# RiseUpTop.net
KiCad netlist of a schematic drawn in EAGLE
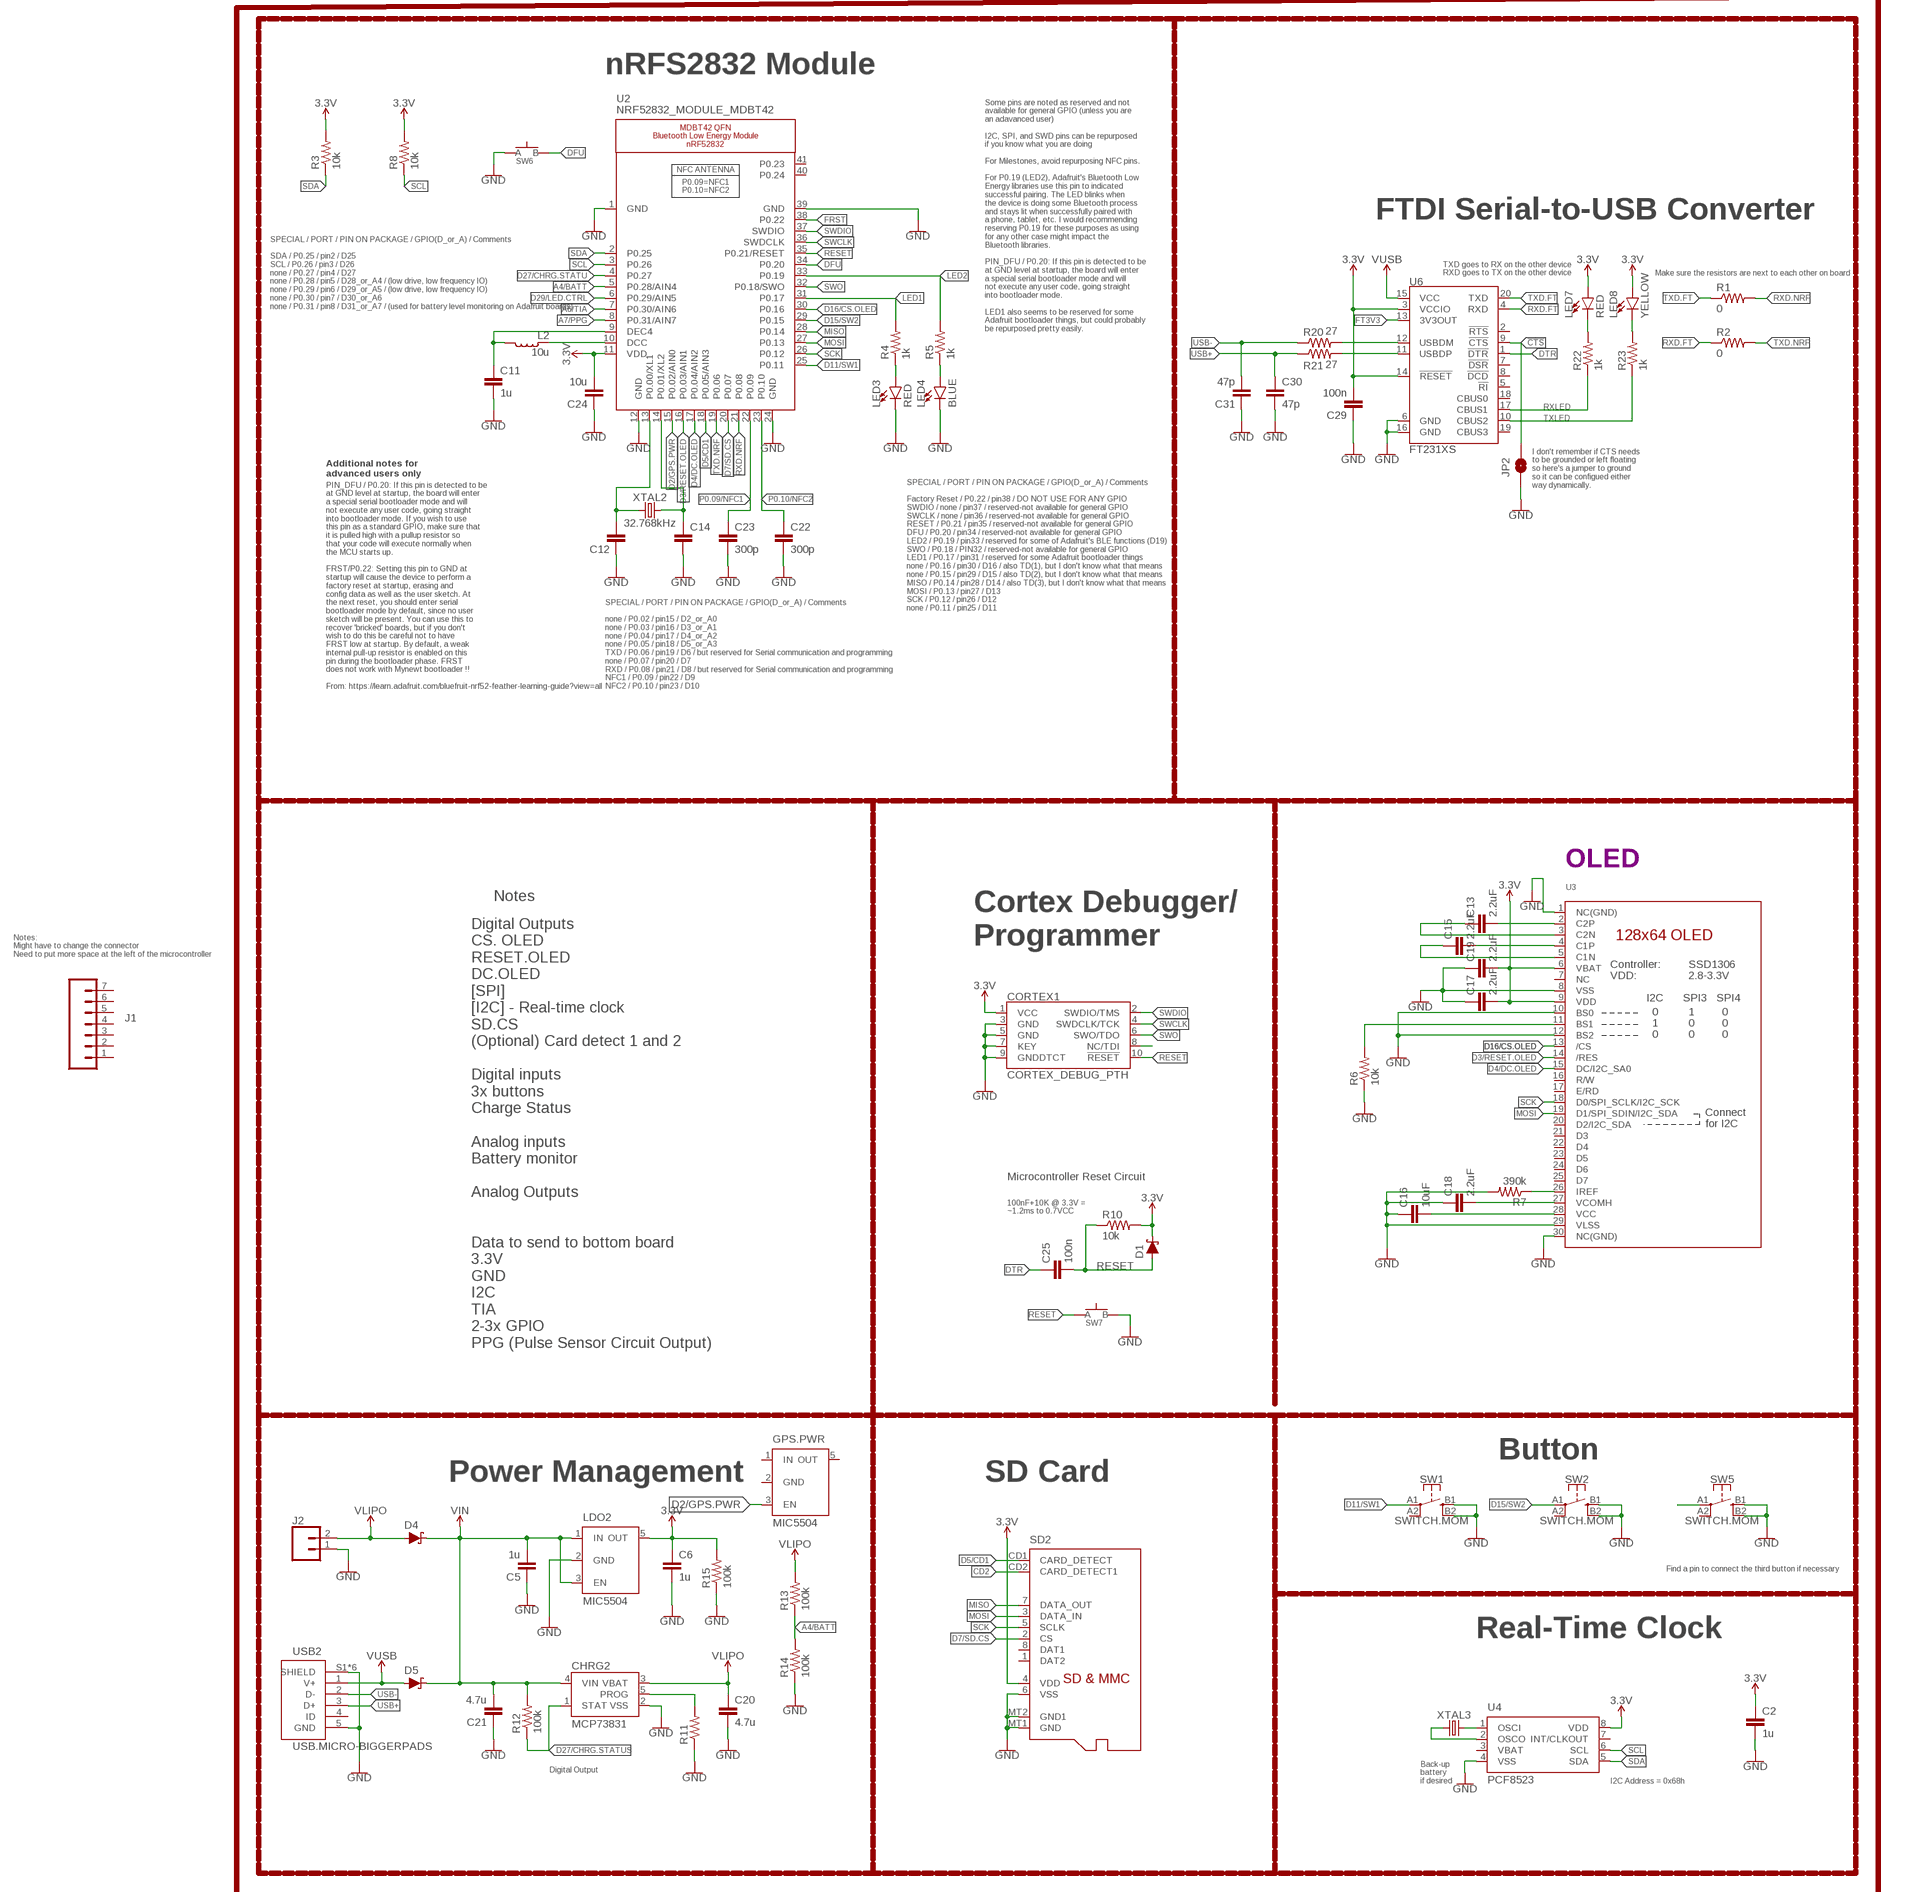
[diagram p0: schematic, sheet 1, part 1 of 2]
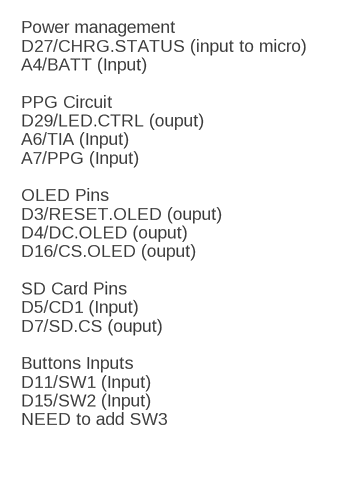
[diagram p1: schematic, sheet 1, part 2 of 2]

(export (version "E")
  (design (tool "Eeschema 10.0.6"))
  (components
    (comp (ref "C2")
      (value "1u")
      (footprint "eagle-import:C0603")
      (libsource (lib "eagle-import") (part "CAPACITOR0603"))
    )
    (comp (ref "C5")
      (value "1u")
      (footprint "eagle-import:C0603")
      (libsource (lib "eagle-import") (part "CAPACITOR0603"))
    )
    (comp (ref "C6")
      (value "1u")
      (footprint "eagle-import:C0603")
      (libsource (lib "eagle-import") (part "CAPACITOR0603"))
    )
    (comp (ref "C11")
      (value "1u")
      (footprint "eagle-import:C0603")
      (libsource (lib "eagle-import") (part "CAPACITOR0603"))
    )
    (comp (ref "C12")
      (value "CAPACITOR0603")
      (footprint "eagle-import:C0603")
      (libsource (lib "eagle-import") (part "CAPACITOR0603"))
    )
    (comp (ref "C13")
      (value "2.2uF")
      (footprint "eagle-import:C0402")
      (libsource (lib "eagle-import") (part "CAPACITOR0402"))
    )
    (comp (ref "C14")
      (value "CAPACITOR0603")
      (footprint "eagle-import:C0603")
      (libsource (lib "eagle-import") (part "CAPACITOR0603"))
    )
    (comp (ref "C15")
      (value "2.2uF")
      (footprint "eagle-import:C0402")
      (libsource (lib "eagle-import") (part "CAPACITOR0402"))
    )
    (comp (ref "C16")
      (value "10uF")
      (footprint "eagle-import:C0603")
      (libsource (lib "eagle-import") (part "CAPACITOR0603"))
    )
    (comp (ref "C17")
      (value "2.2uF")
      (footprint "eagle-import:C0402")
      (libsource (lib "eagle-import") (part "CAPACITOR0402"))
    )
    (comp (ref "C18")
      (value "2.2uF")
      (footprint "eagle-import:C0402")
      (libsource (lib "eagle-import") (part "CAPACITOR0402"))
    )
    (comp (ref "C19")
      (value "2.2uF")
      (footprint "eagle-import:C0402")
      (libsource (lib "eagle-import") (part "CAPACITOR0402"))
    )
    (comp (ref "C20")
      (value "4.7u")
      (footprint "eagle-import:C0603")
      (libsource (lib "eagle-import") (part "CAPACITOR0603"))
    )
    (comp (ref "C21")
      (value "4.7u")
      (footprint "eagle-import:C0603")
      (libsource (lib "eagle-import") (part "CAPACITOR0603"))
    )
    (comp (ref "C22")
      (value "300p")
      (footprint "eagle-import:C0603")
      (libsource (lib "eagle-import") (part "CAPACITOR0603"))
    )
    (comp (ref "C23")
      (value "300p")
      (footprint "eagle-import:C0603")
      (libsource (lib "eagle-import") (part "CAPACITOR0603"))
    )
    (comp (ref "C24")
      (value "10u")
      (footprint "eagle-import:C0805")
      (libsource (lib "eagle-import") (part "CAPACITOR0805"))
    )
    (comp (ref "C25")
      (value "100n")
      (footprint "eagle-import:C0603")
      (libsource (lib "eagle-import") (part "CAPACITOR0603"))
    )
    (comp (ref "C29")
      (value "100n")
      (footprint "eagle-import:C0603")
      (libsource (lib "eagle-import") (part "CAPACITOR0603"))
    )
    (comp (ref "C30")
      (value "47p")
      (footprint "eagle-import:C0603")
      (libsource (lib "eagle-import") (part "CAPACITOR0603"))
    )
    (comp (ref "C31")
      (value "47p")
      (footprint "eagle-import:C0603")
      (libsource (lib "eagle-import") (part "CAPACITOR0603"))
    )
    (comp (ref "CHRG2")
      (value "MCP73831")
      (footprint "eagle-import:SOT23-5")
      (libsource (lib "eagle-import") (part "MCP73831"))
    )
    (comp (ref "CORTEX1")
      (value "CORTEX_DEBUG_PTH")
      (footprint "eagle-import:2X5-PTH-1.27MM")
      (libsource (lib "eagle-import") (part "CORTEX_DEBUG_PTH"))
    )
    (comp (ref "D1")
      (value "SCHOTTKY-USC")
      (footprint "eagle-import:USC")
      (libsource (lib "eagle-import") (part "SCHOTTKY-USC"))
    )
    (comp (ref "D4")
      (value "SCHOTTKY-USC")
      (footprint "eagle-import:USC")
      (libsource (lib "eagle-import") (part "SCHOTTKY-USC"))
    )
    (comp (ref "D5")
      (value "SCHOTTKY-USC")
      (footprint "eagle-import:USC")
      (libsource (lib "eagle-import") (part "SCHOTTKY-USC"))
    )
    (comp (ref "GPS.PWR")
      (value "MIC5504")
      (footprint "eagle-import:SOT23-5")
      (libsource (lib "eagle-import") (part "MIC5504"))
    )
    (comp (ref "J1")
      (value "CONN_07")
      (footprint "eagle-import:1X07")
      (libsource (lib "eagle-import") (part "CONN_07"))
    )
    (comp (ref "J2")
      (value "CONN_02")
      (footprint "eagle-import:1X02")
      (libsource (lib "eagle-import") (part "CONN_02"))
    )
    (comp (ref "JP2")
      (value "JUMPER-SMT_2_NO_SILK")
      (footprint "eagle-import:SMT-JUMPER_2_NO_SILK")
      (libsource (lib "eagle-import") (part "JUMPER-SMT_2_NO_SILK"))
    )
    (comp (ref "L2")
      (value "10u")
      (footprint "eagle-import:L0603")
      (libsource (lib "eagle-import") (part "INDUCTOR0603"))
    )
    (comp (ref "LDO2")
      (value "MIC5504")
      (footprint "eagle-import:SOT23-5")
      (libsource (lib "eagle-import") (part "MIC5504"))
    )
    (comp (ref "LED3")
      (value "RED")
      (footprint "eagle-import:LED-0603")
      (libsource (lib "eagle-import") (part "LED0603"))
    )
    (comp (ref "LED4")
      (value "BLUE")
      (footprint "eagle-import:LED-0603")
      (libsource (lib "eagle-import") (part "LED0603"))
    )
    (comp (ref "LED7")
      (value "RED")
      (footprint "eagle-import:LED-0603")
      (libsource (lib "eagle-import") (part "LED0603"))
    )
    (comp (ref "LED8")
      (value "YELLOW")
      (footprint "eagle-import:LED-0603")
      (libsource (lib "eagle-import") (part "LED0603"))
    )
    (comp (ref "R1")
      (value "0")
      (footprint "eagle-import:R0603")
      (libsource (lib "eagle-import") (part "RESISTOR0603"))
    )
    (comp (ref "R2")
      (value "0")
      (footprint "eagle-import:R0603")
      (libsource (lib "eagle-import") (part "RESISTOR0603"))
    )
    (comp (ref "R3")
      (value "10k")
      (footprint "eagle-import:R0603")
      (libsource (lib "eagle-import") (part "RESISTOR0603"))
    )
    (comp (ref "R4")
      (value "1k")
      (footprint "eagle-import:R0603")
      (libsource (lib "eagle-import") (part "RESISTOR0603"))
    )
    (comp (ref "R5")
      (value "1k")
      (footprint "eagle-import:R0603")
      (libsource (lib "eagle-import") (part "RESISTOR0603"))
    )
    (comp (ref "R6")
      (value "10k")
      (footprint "eagle-import:R0603")
      (libsource (lib "eagle-import") (part "RESISTOR0603"))
    )
    (comp (ref "R7")
      (value "390k")
      (footprint "eagle-import:R0603")
      (libsource (lib "eagle-import") (part "RESISTOR0603"))
    )
    (comp (ref "R8")
      (value "10k")
      (footprint "eagle-import:R0603")
      (libsource (lib "eagle-import") (part "RESISTOR0603"))
    )
    (comp (ref "R10")
      (value "10k")
      (footprint "eagle-import:R0603")
      (libsource (lib "eagle-import") (part "RESISTOR0603"))
    )
    (comp (ref "R11")
      (value "RESISTOR0603")
      (footprint "eagle-import:R0603")
      (libsource (lib "eagle-import") (part "RESISTOR0603"))
    )
    (comp (ref "R12")
      (value "100k")
      (footprint "eagle-import:R0603")
      (libsource (lib "eagle-import") (part "RESISTOR0603"))
    )
    (comp (ref "R13")
      (value "100k")
      (footprint "eagle-import:R0603")
      (libsource (lib "eagle-import") (part "RESISTOR0603"))
    )
    (comp (ref "R14")
      (value "100k")
      (footprint "eagle-import:R0603")
      (libsource (lib "eagle-import") (part "RESISTOR0603"))
    )
    (comp (ref "R15")
      (value "100k")
      (footprint "eagle-import:R0603")
      (libsource (lib "eagle-import") (part "RESISTOR0603"))
    )
    (comp (ref "R20")
      (value "27")
      (footprint "eagle-import:R0603")
      (libsource (lib "eagle-import") (part "RESISTOR0603"))
    )
    (comp (ref "R21")
      (value "27")
      (footprint "eagle-import:R0603")
      (libsource (lib "eagle-import") (part "RESISTOR0603"))
    )
    (comp (ref "R22")
      (value "1k")
      (footprint "eagle-import:R0603")
      (libsource (lib "eagle-import") (part "RESISTOR0603"))
    )
    (comp (ref "R23")
      (value "1k")
      (footprint "eagle-import:R0603")
      (libsource (lib "eagle-import") (part "RESISTOR0603"))
    )
    (comp (ref "SD2")
      (value "MICROSD")
      (footprint "eagle-import:MICROSD")
      (libsource (lib "eagle-import") (part "MICROSD"))
    )
    (comp (ref "SW1")
      (value "SWITCH.MOM")
      (footprint "eagle-import:TACTILE_SWITCH_SMD_6.2MM_TALL")
      (libsource (lib "eagle-import") (part "SWITCH.MOM"))
    )
    (comp (ref "SW2")
      (value "SWITCH.MOM")
      (footprint "eagle-import:TACTILE_SWITCH_SMD_6.2MM_TALL")
      (libsource (lib "eagle-import") (part "SWITCH.MOM"))
    )
    (comp (ref "SW5")
      (value "SWITCH.MOM")
      (footprint "eagle-import:TACTILE_SWITCH_SMD_6.2MM_TALL")
      (libsource (lib "eagle-import") (part "SWITCH.MOM"))
    )
    (comp (ref "SW6")
      (value "SPST-PTS830GG140-COPY.1-3")
      (footprint "eagle-import:BUTTON-GULLWING")
      (libsource (lib "eagle-import") (part "SPST-PTS830GG140-COPY.1-3"))
    )
    (comp (ref "SW7")
      (value "SPST-PTS830GG140-COPY.1-3")
      (footprint "eagle-import:BUTTON-GULLWING")
      (libsource (lib "eagle-import") (part "SPST-PTS830GG140-COPY.1-3"))
    )
    (comp (ref "U2")
      (value "NRF52832_MODULE_MDBT42")
      (footprint "eagle-import:BLE_MODULE_RAYTAC_MDBT42")
      (libsource (lib "eagle-import") (part "NRF52832_MODULE_MDBT42"))
    )
    (comp (ref "U3")
      (value "DISP_OLED_UG-2864HSWEG01-NO-WRAPAROUND")
      (footprint "eagle-import:UG-2864HSWEG01_0.96IN_NO-WRAPAROUND")
      (libsource (lib "eagle-import") (part "DISP_OLED_UG-2864HSWEG01-NO-WRAPAROUND"))
    )
    (comp (ref "U4")
      (value "PCF8523")
      (footprint "eagle-import:SO8")
      (libsource (lib "eagle-import") (part "PCF8523"))
    )
    (comp (ref "U6")
      (value "FT231XS")
      (footprint "eagle-import:SSOP20_L")
      (libsource (lib "eagle-import") (part "FT231XS"))
    )
    (comp (ref "USB2")
      (value "USB.MICRO-BIGGERPADS")
      (footprint "eagle-import:USB-MICRO-01.BIGGERPADS")
      (libsource (lib "eagle-import") (part "USB.MICRO-BIGGERPADS"))
    )
    (comp (ref "XTAL2")
      (value "32.768kHz")
      (footprint "eagle-import:2-SMD.NOLEAD.2.0MMTO1.2MM")
      (libsource (lib "eagle-import") (part "CRYSTALECS-.327-12.5-12-C-TR"))
    )
    (comp (ref "XTAL3")
      (value "32.7680kHz")
      (footprint "eagle-import:2-SMD.NOLEAD.2.0MMTO1.2MM")
      (fields (field (name "FREQ") "32.7680KHZ"))
      (libsource (lib "eagle-import") (part "CRYSTALECS-.327-12.5-12-C-TR"))
    )
  )
  (nets
    (net (code "1") (name "/RXLED") (class "Default")
      (node (ref "R22") (pin "1") (pinfunction "1_1") (pintype "passive"))
      (node (ref "U6") (pin "17") (pinfunction "CBUS1_17") (pintype "bidirectional"))
    )
    (net (code "2") (name "/TXLED") (class "Default")
      (node (ref "R23") (pin "1") (pinfunction "1_1") (pintype "passive"))
      (node (ref "U6") (pin "10") (pinfunction "CBUS2_10") (pintype "bidirectional"))
    )
    (net (code "3") (name "/VBAT") (class "Default")
      (node (ref "U4") (pin "3") (pinfunction "VBAT_3") (pintype "power_in"))
    )
    (net (code "4") (name "/~{CTS}") (class "Default")
      (node (ref "JP2") (pin "2") (pinfunction "2_2") (pintype "passive"))
      (node (ref "U6") (pin "9") (pinfunction "~{CTS}_9") (pintype "bidirectional"))
    )
    (net (code "5") (name "3.3V") (class "Default")
      (node (ref "C17") (pin "2") (pinfunction "2_2") (pintype "passive"))
      (node (ref "C19") (pin "2") (pinfunction "2_2") (pintype "passive"))
      (node (ref "C2") (pin "1") (pinfunction "1_1") (pintype "passive"))
      (node (ref "C24") (pin "2") (pinfunction "2_2") (pintype "passive"))
      (node (ref "C29") (pin "2") (pinfunction "2_2") (pintype "passive"))
      (node (ref "C6") (pin "1") (pinfunction "1_1") (pintype "passive"))
      (node (ref "CORTEX1") (pin "1") (pinfunction "VCC_1") (pintype "bidirectional"))
      (node (ref "D1") (pin "-") (pinfunction "C_-") (pintype "passive"))
      (node (ref "LDO2") (pin "5") (pinfunction "OUT_5") (pintype "bidirectional"))
      (node (ref "LED7") (pin "A") (pinfunction "A_A") (pintype "passive"))
      (node (ref "LED8") (pin "A") (pinfunction "A_A") (pintype "passive"))
      (node (ref "R10") (pin "2") (pinfunction "2_2") (pintype "passive"))
      (node (ref "R15") (pin "2") (pinfunction "2_2") (pintype "passive"))
      (node (ref "R3") (pin "2") (pinfunction "2_2") (pintype "passive"))
      (node (ref "R8") (pin "2") (pinfunction "2_2") (pintype "passive"))
      (node (ref "SD2") (pin "4") (pinfunction "VDD_4") (pintype "power_in"))
      (node (ref "U2") (pin "11") (pinfunction "VDD_11") (pintype "bidirectional"))
      (node (ref "U3") (pin "6") (pinfunction "VBAT_6") (pintype "input"))
      (node (ref "U3") (pin "9") (pinfunction "VDD_9") (pintype "power_in"))
      (node (ref "U4") (pin "8") (pinfunction "VDD_8") (pintype "power_in"))
      (node (ref "U6") (pin "14") (pinfunction "~{RESET}_14") (pintype "bidirectional"))
      (node (ref "U6") (pin "3") (pinfunction "VCCIO_3") (pintype "bidirectional"))
    )
    (net (code "6") (name "A4{slash}BATT") (class "Default")
      (node (ref "R13") (pin "1") (pinfunction "1_1") (pintype "passive"))
      (node (ref "R14") (pin "2") (pinfunction "2_2") (pintype "passive"))
      (node (ref "U2") (pin "5") (pinfunction "P0.28/AIN4_5") (pintype "bidirectional"))
    )
    (net (code "7") (name "A6{slash}TIA") (class "Default")
      (node (ref "U2") (pin "7") (pinfunction "P0.30/AIN6_7") (pintype "bidirectional"))
    )
    (net (code "8") (name "A7{slash}PPG") (class "Default")
      (node (ref "U2") (pin "8") (pinfunction "P0.31/AIN7_8") (pintype "bidirectional"))
    )
    (net (code "9") (name "CD2") (class "Default")
      (node (ref "SD2") (pin "CD2") (pinfunction "CARD_DETECT1_CD2") (pintype "passive"))
    )
    (net (code "10") (name "D2{slash}GPS.PWR") (class "Default")
      (node (ref "GPS.PWR") (pin "3") (pinfunction "EN_3") (pintype "bidirectional"))
      (node (ref "U2") (pin "15") (pinfunction "P0.02/AIN0_15") (pintype "bidirectional"))
    )
    (net (code "11") (name "D3{slash}RESET.OLED") (class "Default")
      (node (ref "U2") (pin "16") (pinfunction "P0.03/AIN1_16") (pintype "bidirectional"))
      (node (ref "U3") (pin "14") (pinfunction "/RES_14") (pintype "input"))
    )
    (net (code "12") (name "D4{slash}DC.OLED") (class "Default")
      (node (ref "U2") (pin "17") (pinfunction "P0.04/AIN2_17") (pintype "bidirectional"))
      (node (ref "U3") (pin "15") (pinfunction "DC/I2C_SA0_15") (pintype "input"))
    )
    (net (code "13") (name "D5{slash}CD1") (class "Default")
      (node (ref "SD2") (pin "CD1") (pinfunction "CARD_DETECT_CD1") (pintype "passive"))
      (node (ref "U2") (pin "18") (pinfunction "P0.05/AIN3_18") (pintype "bidirectional"))
    )
    (net (code "14") (name "D7{slash}SD.CS") (class "Default")
      (node (ref "SD2") (pin "2") (pinfunction "CS_2") (pintype "input"))
      (node (ref "U2") (pin "20") (pinfunction "P0.07_20") (pintype "bidirectional"))
    )
    (net (code "15") (name "D11{slash}SW1") (class "Default")
      (node (ref "SW1") (pin "A1") (pinfunction "1_A1") (pintype "passive"))
      (node (ref "U2") (pin "25") (pinfunction "P0.11_25") (pintype "bidirectional"))
    )
    (net (code "16") (name "D15{slash}SW2") (class "Default")
      (node (ref "SW2") (pin "A1") (pinfunction "1_A1") (pintype "passive"))
      (node (ref "U2") (pin "29") (pinfunction "P0.15_29") (pintype "bidirectional"))
    )
    (net (code "17") (name "D16{slash}CS.OLED") (class "Default")
      (node (ref "U2") (pin "30") (pinfunction "P0.16_30") (pintype "bidirectional"))
      (node (ref "U3") (pin "13") (pinfunction "/CS_13") (pintype "input"))
    )
    (net (code "18") (name "D27{slash}CHRG.STATU") (class "Default")
      (node (ref "U2") (pin "4") (pinfunction "P0.27_4") (pintype "bidirectional"))
    )
    (net (code "19") (name "D27{slash}CHRG.STATUS") (class "Default")
      (node (ref "CHRG2") (pin "1") (pinfunction "STAT_1") (pintype "output"))
      (node (ref "R12") (pin "1") (pinfunction "1_1") (pintype "passive"))
    )
    (net (code "20") (name "D29{slash}LED.CTRL") (class "Default")
      (node (ref "U2") (pin "6") (pinfunction "P0.29/AIN5_6") (pintype "bidirectional"))
    )
    (net (code "21") (name "DFU") (class "Default")
      (node (ref "SW6") (pin "3") (pinfunction "B_3") (pintype "bidirectional"))
      (node (ref "U2") (pin "34") (pinfunction "P0.20_34") (pintype "bidirectional"))
    )
    (net (code "22") (name "DTR") (class "Default")
      (node (ref "C25") (pin "1") (pinfunction "1_1") (pintype "passive"))
      (node (ref "U6") (pin "1") (pinfunction "~{DTR}_1") (pintype "bidirectional"))
    )
    (net (code "23") (name "FRST") (class "Default")
      (node (ref "U2") (pin "38") (pinfunction "P0.22_38") (pintype "bidirectional"))
    )
    (net (code "24") (name "FT3V3") (class "Default")
      (node (ref "U6") (pin "13") (pinfunction "3V3OUT_13") (pintype "bidirectional"))
    )
    (net (code "25") (name "GND") (class "Default")
      (node (ref "C11") (pin "2") (pinfunction "2_2") (pintype "passive"))
      (node (ref "C12") (pin "1") (pinfunction "1_1") (pintype "passive"))
      (node (ref "C14") (pin "2") (pinfunction "2_2") (pintype "passive"))
      (node (ref "C16") (pin "1") (pinfunction "1_1") (pintype "passive"))
      (node (ref "C17") (pin "1") (pinfunction "1_1") (pintype "passive"))
      (node (ref "C18") (pin "1") (pinfunction "1_1") (pintype "passive"))
      (node (ref "C19") (pin "1") (pinfunction "1_1") (pintype "passive"))
      (node (ref "C2") (pin "2") (pinfunction "2_2") (pintype "passive"))
      (node (ref "C20") (pin "2") (pinfunction "2_2") (pintype "passive"))
      (node (ref "C21") (pin "1") (pinfunction "1_1") (pintype "passive"))
      (node (ref "C22") (pin "2") (pinfunction "2_2") (pintype "passive"))
      (node (ref "C23") (pin "2") (pinfunction "2_2") (pintype "passive"))
      (node (ref "C24") (pin "1") (pinfunction "1_1") (pintype "passive"))
      (node (ref "C29") (pin "1") (pinfunction "1_1") (pintype "passive"))
      (node (ref "C30") (pin "2") (pinfunction "2_2") (pintype "passive"))
      (node (ref "C31") (pin "1") (pinfunction "1_1") (pintype "passive"))
      (node (ref "C5") (pin "1") (pinfunction "1_1") (pintype "passive"))
      (node (ref "C6") (pin "2") (pinfunction "2_2") (pintype "passive"))
      (node (ref "CHRG2") (pin "2") (pinfunction "VSS_2") (pintype "power_in"))
      (node (ref "CORTEX1") (pin "3") (pinfunction "GND_3") (pintype "bidirectional"))
      (node (ref "CORTEX1") (pin "5") (pinfunction "GND_5") (pintype "bidirectional"))
      (node (ref "CORTEX1") (pin "7") (pinfunction "KEY_7") (pintype "bidirectional"))
      (node (ref "CORTEX1") (pin "9") (pinfunction "GNDDTCT_9") (pintype "bidirectional"))
      (node (ref "J2") (pin "1") (pinfunction "1_1") (pintype "passive"))
      (node (ref "JP2") (pin "1") (pinfunction "1_1") (pintype "passive"))
      (node (ref "LDO2") (pin "2") (pinfunction "GND_2") (pintype "bidirectional"))
      (node (ref "LED3") (pin "C") (pinfunction "C_C") (pintype "passive"))
      (node (ref "LED4") (pin "C") (pinfunction "C_C") (pintype "passive"))
      (node (ref "R11") (pin "1") (pinfunction "1_1") (pintype "passive"))
      (node (ref "R14") (pin "1") (pinfunction "1_1") (pintype "passive"))
      (node (ref "R15") (pin "1") (pinfunction "1_1") (pintype "passive"))
      (node (ref "R6") (pin "1") (pinfunction "1_1") (pintype "passive"))
      (node (ref "R7") (pin "2") (pinfunction "2_2") (pintype "passive"))
      (node (ref "SD2") (pin "6") (pinfunction "VSS_6") (pintype "power_in"))
      (node (ref "SD2") (pin "MT1") (pinfunction "GND_MT1") (pintype "power_in"))
      (node (ref "SD2") (pin "MT2") (pinfunction "GND1_MT2") (pintype "power_in"))
      (node (ref "SW1") (pin "B1") (pinfunction "3_B1") (pintype "passive"))
      (node (ref "SW1") (pin "B2") (pinfunction "4_B2") (pintype "passive"))
      (node (ref "SW2") (pin "B1") (pinfunction "3_B1") (pintype "passive"))
      (node (ref "SW2") (pin "B2") (pinfunction "4_B2") (pintype "passive"))
      (node (ref "SW5") (pin "B1") (pinfunction "3_B1") (pintype "passive"))
      (node (ref "SW5") (pin "B2") (pinfunction "4_B2") (pintype "passive"))
      (node (ref "SW6") (pin "1") (pinfunction "A_1") (pintype "bidirectional"))
      (node (ref "SW7") (pin "3") (pinfunction "B_3") (pintype "bidirectional"))
      (node (ref "U2") (pin "1") (pinfunction "GND_1") (pintype "bidirectional"))
      (node (ref "U2") (pin "12") (pinfunction "GND_12") (pintype "bidirectional"))
      (node (ref "U2") (pin "24") (pinfunction "GND_24") (pintype "bidirectional"))
      (node (ref "U2") (pin "39") (pinfunction "GND_39") (pintype "bidirectional"))
      (node (ref "U3") (pin "1") (pinfunction "NC(GND)_1") (pintype "input"))
      (node (ref "U3") (pin "10") (pinfunction "BS0_10") (pintype "input"))
      (node (ref "U3") (pin "12") (pinfunction "BS2_12") (pintype "input"))
      (node (ref "U3") (pin "29") (pinfunction "VLSS_29") (pintype "power_in"))
      (node (ref "U3") (pin "30") (pinfunction "NC(GND)_30") (pintype "input"))
      (node (ref "U3") (pin "8") (pinfunction "VSS_8") (pintype "power_in"))
      (node (ref "U4") (pin "4") (pinfunction "VSS_4") (pintype "power_in"))
      (node (ref "U6") (pin "16") (pinfunction "GND_16") (pintype "bidirectional"))
      (node (ref "U6") (pin "6") (pinfunction "GND_6") (pintype "bidirectional"))
      (node (ref "USB2") (pin "5") (pinfunction "GND_5") (pintype "bidirectional"))
      (node (ref "USB2") (pin "S1") (pinfunction "SHIELD_S1") (pintype "bidirectional"))
      (node (ref "USB2") (pin "S2") (pinfunction "SHIELD_S2") (pintype "bidirectional"))
      (node (ref "USB2") (pin "S3") (pinfunction "SHIELD_S3") (pintype "bidirectional"))
      (node (ref "USB2") (pin "S4") (pinfunction "SHIELD_S4") (pintype "bidirectional"))
      (node (ref "USB2") (pin "S5") (pinfunction "SHIELD_S5") (pintype "bidirectional"))
      (node (ref "USB2") (pin "S6") (pinfunction "SHIELD_S6") (pintype "bidirectional"))
    )
    (net (code "26") (name "LED1") (class "Default")
      (node (ref "R4") (pin "2") (pinfunction "2_2") (pintype "passive"))
      (node (ref "U2") (pin "31") (pinfunction "P0.17_31") (pintype "bidirectional"))
    )
    (net (code "27") (name "LED2") (class "Default")
      (node (ref "R5") (pin "2") (pinfunction "2_2") (pintype "passive"))
      (node (ref "U2") (pin "33") (pinfunction "P0.19_33") (pintype "bidirectional"))
    )
    (net (code "28") (name "MISO") (class "Default")
      (node (ref "SD2") (pin "7") (pinfunction "DATA_OUT_7") (pintype "output"))
      (node (ref "U2") (pin "28") (pinfunction "P0.14_28") (pintype "bidirectional"))
    )
    (net (code "29") (name "MOSI") (class "Default")
      (node (ref "SD2") (pin "3") (pinfunction "DATA_IN_3") (pintype "input"))
      (node (ref "U2") (pin "27") (pinfunction "P0.13_27") (pintype "bidirectional"))
      (node (ref "U3") (pin "19") (pinfunction "D1/SPI_SDIN/I2C_SDA_19") (pintype "bidirectional"))
    )
    (net (code "30") (name "Net-(CHRG2-PROG)") (class "Default")
      (node (ref "CHRG2") (pin "5") (pinfunction "PROG_5") (pintype "input"))
      (node (ref "R11") (pin "2") (pinfunction "2_2") (pintype "passive"))
    )
    (net (code "31") (name "Net-(LED3-PadA)") (class "Default")
      (node (ref "LED3") (pin "A") (pinfunction "A_A") (pintype "passive"))
      (node (ref "R4") (pin "1") (pinfunction "1_1") (pintype "passive"))
    )
    (net (code "32") (name "Net-(LED4-PadA)") (class "Default")
      (node (ref "LED4") (pin "A") (pinfunction "A_A") (pintype "passive"))
      (node (ref "R5") (pin "1") (pinfunction "1_1") (pintype "passive"))
    )
    (net (code "33") (name "Net-(LED7-PadC)") (class "Default")
      (node (ref "LED7") (pin "C") (pinfunction "C_C") (pintype "passive"))
      (node (ref "R22") (pin "2") (pinfunction "2_2") (pintype "passive"))
    )
    (net (code "34") (name "Net-(LED8-PadC)") (class "Default")
      (node (ref "LED8") (pin "C") (pinfunction "C_C") (pintype "passive"))
      (node (ref "R23") (pin "2") (pinfunction "2_2") (pintype "passive"))
    )
    (net (code "35") (name "Net-(U2-DCC)") (class "Default")
      (node (ref "L2") (pin "1") (pinfunction "1_1") (pintype "passive"))
      (node (ref "U2") (pin "10") (pinfunction "DCC_10") (pintype "bidirectional"))
    )
    (net (code "36") (name "Net-(U2-DEC4)") (class "Default")
      (node (ref "C11") (pin "1") (pinfunction "1_1") (pintype "passive"))
      (node (ref "L2") (pin "2") (pinfunction "2_2") (pintype "passive"))
      (node (ref "U2") (pin "9") (pinfunction "DEC4_9") (pintype "bidirectional"))
    )
    (net (code "37") (name "Net-(U2-P0.00{slash}XL1)") (class "Default")
      (node (ref "C12") (pin "2") (pinfunction "2_2") (pintype "passive"))
      (node (ref "U2") (pin "13") (pinfunction "P0.00/XL1_13") (pintype "bidirectional"))
      (node (ref "XTAL2") (pin "P$1") (pinfunction "1_P$1") (pintype "passive"))
    )
    (net (code "38") (name "Net-(U2-P0.01{slash}XL2)") (class "Default")
      (node (ref "C14") (pin "1") (pinfunction "1_1") (pintype "passive"))
      (node (ref "U2") (pin "14") (pinfunction "P0.01/XL2_14") (pintype "bidirectional"))
      (node (ref "XTAL2") (pin "P$2") (pinfunction "2_P$2") (pintype "passive"))
    )
    (net (code "39") (name "Net-(U3-BS1)") (class "Default")
      (node (ref "R6") (pin "2") (pinfunction "2_2") (pintype "passive"))
      (node (ref "U3") (pin "11") (pinfunction "BS1_11") (pintype "input"))
    )
    (net (code "40") (name "Net-(U3-C1N)") (class "Default")
      (node (ref "C15") (pin "1") (pinfunction "1_1") (pintype "passive"))
      (node (ref "U3") (pin "5") (pinfunction "C1N_5") (pintype "input"))
    )
    (net (code "41") (name "Net-(U3-C1P)") (class "Default")
      (node (ref "C15") (pin "2") (pinfunction "2_2") (pintype "passive"))
      (node (ref "U3") (pin "4") (pinfunction "C1P_4") (pintype "input"))
    )
    (net (code "42") (name "Net-(U3-C2N)") (class "Default")
      (node (ref "C13") (pin "1") (pinfunction "1_1") (pintype "passive"))
      (node (ref "U3") (pin "3") (pinfunction "C2N_3") (pintype "input"))
    )
    (net (code "43") (name "Net-(U3-C2P)") (class "Default")
      (node (ref "C13") (pin "2") (pinfunction "2_2") (pintype "passive"))
      (node (ref "U3") (pin "2") (pinfunction "C2P_2") (pintype "input"))
    )
    (net (code "44") (name "Net-(U3-IREF)") (class "Default")
      (node (ref "R7") (pin "1") (pinfunction "1_1") (pintype "passive"))
      (node (ref "U3") (pin "26") (pinfunction "IREF_26") (pintype "input"))
    )
    (net (code "45") (name "Net-(U3-VCC)") (class "Default")
      (node (ref "C16") (pin "2") (pinfunction "2_2") (pintype "passive"))
      (node (ref "U3") (pin "28") (pinfunction "VCC_28") (pintype "power_in"))
    )
    (net (code "46") (name "Net-(U3-VCOMH)") (class "Default")
      (node (ref "C18") (pin "2") (pinfunction "2_2") (pintype "passive"))
      (node (ref "U3") (pin "27") (pinfunction "VCOMH_27") (pintype "output"))
    )
    (net (code "47") (name "Net-(U4-OSCI)") (class "Default")
      (node (ref "U4") (pin "1") (pinfunction "OSCI_1") (pintype "bidirectional"))
      (node (ref "XTAL3") (pin "P$2") (pinfunction "2_P$2") (pintype "passive"))
    )
    (net (code "48") (name "Net-(U4-OSCO)") (class "Default")
      (node (ref "U4") (pin "2") (pinfunction "OSCO_2") (pintype "bidirectional"))
      (node (ref "XTAL3") (pin "P$1") (pinfunction "1_P$1") (pintype "passive"))
    )
    (net (code "49") (name "Net-(U6-USBDM)") (class "Default")
      (node (ref "R20") (pin "2") (pinfunction "2_2") (pintype "passive"))
      (node (ref "U6") (pin "12") (pinfunction "USBDM_12") (pintype "bidirectional"))
    )
    (net (code "50") (name "Net-(U6-USBDP)") (class "Default")
      (node (ref "R21") (pin "2") (pinfunction "2_2") (pintype "passive"))
      (node (ref "U6") (pin "11") (pinfunction "USBDP_11") (pintype "bidirectional"))
    )
    (net (code "51") (name "P0.09{slash}NFC1") (class "Default")
      (node (ref "C23") (pin "1") (pinfunction "1_1") (pintype "passive"))
      (node (ref "U2") (pin "22") (pinfunction "P0.09_22") (pintype "bidirectional"))
    )
    (net (code "52") (name "P0.10{slash}NFC2") (class "Default")
      (node (ref "C22") (pin "1") (pinfunction "1_1") (pintype "passive"))
      (node (ref "U2") (pin "23") (pinfunction "P0.10_23") (pintype "bidirectional"))
    )
    (net (code "53") (name "RESET") (class "Default")
      (node (ref "C25") (pin "2") (pinfunction "2_2") (pintype "passive"))
      (node (ref "CORTEX1") (pin "10") (pinfunction "~{RESET}_10") (pintype "bidirectional"))
      (node (ref "D1") (pin "+") (pinfunction "A_+") (pintype "passive"))
      (node (ref "R10") (pin "1") (pinfunction "1_1") (pintype "passive"))
      (node (ref "SW7") (pin "1") (pinfunction "A_1") (pintype "bidirectional"))
      (node (ref "U2") (pin "35") (pinfunction "P0.21/RESET_35") (pintype "bidirectional"))
    )
    (net (code "54") (name "RXD.FT") (class "Default")
      (node (ref "R2") (pin "1") (pinfunction "1_1") (pintype "passive"))
      (node (ref "U6") (pin "4") (pinfunction "RXD_4") (pintype "bidirectional"))
    )
    (net (code "55") (name "RXD.NRF") (class "Default")
      (node (ref "R1") (pin "2") (pinfunction "2_2") (pintype "passive"))
      (node (ref "U2") (pin "21") (pinfunction "P0.08_21") (pintype "bidirectional"))
    )
    (net (code "56") (name "SCK") (class "Default")
      (node (ref "SD2") (pin "5") (pinfunction "SCLK_5") (pintype "input"))
      (node (ref "U2") (pin "26") (pinfunction "P0.12_26") (pintype "bidirectional"))
      (node (ref "U3") (pin "18") (pinfunction "D0/SPI_SCLK/I2C_SCK_18") (pintype "bidirectional"))
    )
    (net (code "57") (name "SCL") (class "Default")
      (node (ref "R8") (pin "1") (pinfunction "1_1") (pintype "passive"))
      (node (ref "U2") (pin "3") (pinfunction "P0.26_3") (pintype "bidirectional"))
      (node (ref "U4") (pin "6") (pinfunction "SCL_6") (pintype "bidirectional"))
    )
    (net (code "58") (name "SDA") (class "Default")
      (node (ref "R3") (pin "1") (pinfunction "1_1") (pintype "passive"))
      (node (ref "U2") (pin "2") (pinfunction "P0.25_2") (pintype "bidirectional"))
      (node (ref "U4") (pin "5") (pinfunction "SDA_5") (pintype "bidirectional"))
    )
    (net (code "59") (name "SWCLK") (class "Default")
      (node (ref "CORTEX1") (pin "4") (pinfunction "SWDCLK/TCK_4") (pintype "bidirectional"))
      (node (ref "U2") (pin "36") (pinfunction "SWDCLK_36") (pintype "bidirectional"))
    )
    (net (code "60") (name "SWDIO") (class "Default")
      (node (ref "CORTEX1") (pin "2") (pinfunction "SWDIO/TMS_2") (pintype "bidirectional"))
      (node (ref "U2") (pin "37") (pinfunction "SWDIO_37") (pintype "bidirectional"))
    )
    (net (code "61") (name "SWO") (class "Default")
      (node (ref "CORTEX1") (pin "6") (pinfunction "SWO/TDO_6") (pintype "bidirectional"))
      (node (ref "U2") (pin "32") (pinfunction "P0.18/SWO_32") (pintype "bidirectional"))
    )
    (net (code "62") (name "TXD.FT") (class "Default")
      (node (ref "R1") (pin "1") (pinfunction "1_1") (pintype "passive"))
      (node (ref "U6") (pin "20") (pinfunction "TXD_20") (pintype "bidirectional"))
    )
    (net (code "63") (name "TXD.NRF") (class "Default")
      (node (ref "R2") (pin "2") (pinfunction "2_2") (pintype "passive"))
      (node (ref "U2") (pin "19") (pinfunction "P0.06_19") (pintype "bidirectional"))
    )
    (net (code "64") (name "USB+") (class "Default")
      (node (ref "C30") (pin "1") (pinfunction "1_1") (pintype "passive"))
      (node (ref "R21") (pin "1") (pinfunction "1_1") (pintype "passive"))
      (node (ref "USB2") (pin "3") (pinfunction "D+_3") (pintype "bidirectional"))
    )
    (net (code "65") (name "USB-") (class "Default")
      (node (ref "C31") (pin "2") (pinfunction "2_2") (pintype "passive"))
      (node (ref "R20") (pin "1") (pinfunction "1_1") (pintype "passive"))
      (node (ref "USB2") (pin "2") (pinfunction "D-_2") (pintype "bidirectional"))
    )
    (net (code "66") (name "VIN") (class "Default")
      (node (ref "C21") (pin "2") (pinfunction "2_2") (pintype "passive"))
      (node (ref "C5") (pin "2") (pinfunction "2_2") (pintype "passive"))
      (node (ref "CHRG2") (pin "4") (pinfunction "VIN_4") (pintype "power_in"))
      (node (ref "D4") (pin "-") (pinfunction "C_-") (pintype "passive"))
      (node (ref "D5") (pin "-") (pinfunction "C_-") (pintype "passive"))
      (node (ref "LDO2") (pin "1") (pinfunction "IN_1") (pintype "bidirectional"))
      (node (ref "LDO2") (pin "3") (pinfunction "EN_3") (pintype "bidirectional"))
      (node (ref "R12") (pin "2") (pinfunction "2_2") (pintype "passive"))
    )
    (net (code "67") (name "VLIPO") (class "Default")
      (node (ref "C20") (pin "1") (pinfunction "1_1") (pintype "passive"))
      (node (ref "CHRG2") (pin "3") (pinfunction "VBAT_3") (pintype "power_in"))
      (node (ref "D4") (pin "+") (pinfunction "A_+") (pintype "passive"))
      (node (ref "J2") (pin "2") (pinfunction "2_2") (pintype "passive"))
      (node (ref "R13") (pin "2") (pinfunction "2_2") (pintype "passive"))
    )
    (net (code "68") (name "VUSB") (class "Default")
      (node (ref "D5") (pin "+") (pinfunction "A_+") (pintype "passive"))
      (node (ref "U6") (pin "15") (pinfunction "VCC_15") (pintype "bidirectional"))
      (node (ref "USB2") (pin "1") (pinfunction "V+_1") (pintype "bidirectional"))
    )
    (net (code "69") (name "unconnected-(CORTEX1-NC{slash}TDI-Pad8)") (class "Default")
      (node (ref "CORTEX1") (pin "8") (pinfunction "NC/TDI_8") (pintype "bidirectional"))
    )
    (net (code "70") (name "unconnected-(GPS.PWR-GND-Pad2)") (class "Default")
      (node (ref "GPS.PWR") (pin "2") (pinfunction "GND_2") (pintype "bidirectional"))
    )
    (net (code "71") (name "unconnected-(GPS.PWR-IN-Pad1)") (class "Default")
      (node (ref "GPS.PWR") (pin "1") (pinfunction "IN_1") (pintype "bidirectional"))
    )
    (net (code "72") (name "unconnected-(GPS.PWR-OUT-Pad5)") (class "Default")
      (node (ref "GPS.PWR") (pin "5") (pinfunction "OUT_5") (pintype "bidirectional"))
    )
    (net (code "73") (name "unconnected-(J1-Pad1)") (class "Default")
      (node (ref "J1") (pin "1") (pinfunction "1_1") (pintype "passive"))
    )
    (net (code "74") (name "unconnected-(J1-Pad2)") (class "Default")
      (node (ref "J1") (pin "2") (pinfunction "2_2") (pintype "passive"))
    )
    (net (code "75") (name "unconnected-(J1-Pad3)") (class "Default")
      (node (ref "J1") (pin "3") (pinfunction "3_3") (pintype "passive"))
    )
    (net (code "76") (name "unconnected-(J1-Pad4)") (class "Default")
      (node (ref "J1") (pin "4") (pinfunction "4_4") (pintype "passive"))
    )
    (net (code "77") (name "unconnected-(J1-Pad5)") (class "Default")
      (node (ref "J1") (pin "5") (pinfunction "5_5") (pintype "passive"))
    )
    (net (code "78") (name "unconnected-(J1-Pad6)") (class "Default")
      (node (ref "J1") (pin "6") (pinfunction "6_6") (pintype "passive"))
    )
    (net (code "79") (name "unconnected-(J1-Pad7)") (class "Default")
      (node (ref "J1") (pin "7") (pinfunction "7_7") (pintype "passive"))
    )
    (net (code "80") (name "unconnected-(SD2-DAT1-Pad8)") (class "Default")
      (node (ref "SD2") (pin "8") (pinfunction "DAT1_8") (pintype "bidirectional"))
    )
    (net (code "81") (name "unconnected-(SD2-DAT2-Pad1)") (class "Default")
      (node (ref "SD2") (pin "1") (pinfunction "DAT2_1") (pintype "bidirectional"))
    )
    (net (code "82") (name "unconnected-(SW1-2-PadA2)") (class "Default")
      (node (ref "SW1") (pin "A2") (pinfunction "2_A2") (pintype "passive"))
    )
    (net (code "83") (name "unconnected-(SW2-2-PadA2)") (class "Default")
      (node (ref "SW2") (pin "A2") (pinfunction "2_A2") (pintype "passive"))
    )
    (net (code "84") (name "unconnected-(SW5-1-PadA1)") (class "Default")
      (node (ref "SW5") (pin "A1") (pinfunction "1_A1") (pintype "passive"))
    )
    (net (code "85") (name "unconnected-(SW5-2-PadA2)") (class "Default")
      (node (ref "SW5") (pin "A2") (pinfunction "2_A2") (pintype "passive"))
    )
    (net (code "86") (name "unconnected-(U2-P0.23-Pad41)") (class "Default")
      (node (ref "U2") (pin "41") (pinfunction "P0.23_41") (pintype "bidirectional"))
    )
    (net (code "87") (name "unconnected-(U2-P0.24-Pad40)") (class "Default")
      (node (ref "U2") (pin "40") (pinfunction "P0.24_40") (pintype "bidirectional"))
    )
    (net (code "88") (name "unconnected-(U3-D2{slash}I2C_SDA-Pad20)") (class "Default")
      (node (ref "U3") (pin "20") (pinfunction "D2/I2C_SDA_20") (pintype "bidirectional"))
    )
    (net (code "89") (name "unconnected-(U3-D3-Pad21)") (class "Default")
      (node (ref "U3") (pin "21") (pinfunction "D3_21") (pintype "bidirectional"))
    )
    (net (code "90") (name "unconnected-(U3-D4-Pad22)") (class "Default")
      (node (ref "U3") (pin "22") (pinfunction "D4_22") (pintype "bidirectional"))
    )
    (net (code "91") (name "unconnected-(U3-D5-Pad23)") (class "Default")
      (node (ref "U3") (pin "23") (pinfunction "D5_23") (pintype "bidirectional"))
    )
    (net (code "92") (name "unconnected-(U3-D6-Pad24)") (class "Default")
      (node (ref "U3") (pin "24") (pinfunction "D6_24") (pintype "bidirectional"))
    )
    (net (code "93") (name "unconnected-(U3-D7-Pad25)") (class "Default")
      (node (ref "U3") (pin "25") (pinfunction "D7_25") (pintype "bidirectional"))
    )
    (net (code "94") (name "unconnected-(U3-E{slash}RD-Pad17)") (class "Default")
      (node (ref "U3") (pin "17") (pinfunction "E/RD_17") (pintype "input"))
    )
    (net (code "95") (name "unconnected-(U3-NC-Pad7)") (class "Default")
      (node (ref "U3") (pin "7") (pinfunction "NC_7") (pintype "no_connect"))
    )
    (net (code "96") (name "unconnected-(U3-R{slash}W-Pad16)") (class "Default")
      (node (ref "U3") (pin "16") (pinfunction "R/W_16") (pintype "input"))
    )
    (net (code "97") (name "unconnected-(U4-INT{slash}CLKOUT-Pad7)") (class "Default")
      (node (ref "U4") (pin "7") (pinfunction "INT/CLKOUT_7") (pintype "bidirectional"))
    )
    (net (code "98") (name "unconnected-(U6-CBUS0-Pad18)") (class "Default")
      (node (ref "U6") (pin "18") (pinfunction "CBUS0_18") (pintype "bidirectional"))
    )
    (net (code "99") (name "unconnected-(U6-CBUS3-Pad19)") (class "Default")
      (node (ref "U6") (pin "19") (pinfunction "CBUS3_19") (pintype "bidirectional"))
    )
    (net (code "100") (name "unconnected-(U6-~{DCD}-Pad8)") (class "Default")
      (node (ref "U6") (pin "8") (pinfunction "~{DCD}_8") (pintype "bidirectional"))
    )
    (net (code "101") (name "unconnected-(U6-~{DSR}-Pad7)") (class "Default")
      (node (ref "U6") (pin "7") (pinfunction "~{DSR}_7") (pintype "bidirectional"))
    )
    (net (code "102") (name "unconnected-(U6-~{RI}-Pad5)") (class "Default")
      (node (ref "U6") (pin "5") (pinfunction "~{RI}_5") (pintype "bidirectional"))
    )
    (net (code "103") (name "unconnected-(U6-~{RTS}-Pad2)") (class "Default")
      (node (ref "U6") (pin "2") (pinfunction "~{RTS}_2") (pintype "bidirectional"))
    )
    (net (code "104") (name "unconnected-(USB2-ID-Pad4)") (class "Default")
      (node (ref "USB2") (pin "4") (pinfunction "ID_4") (pintype "bidirectional"))
    )
  )
)
